# LEDs.net
KiCad netlist of a schematic drawn in Altium Designer
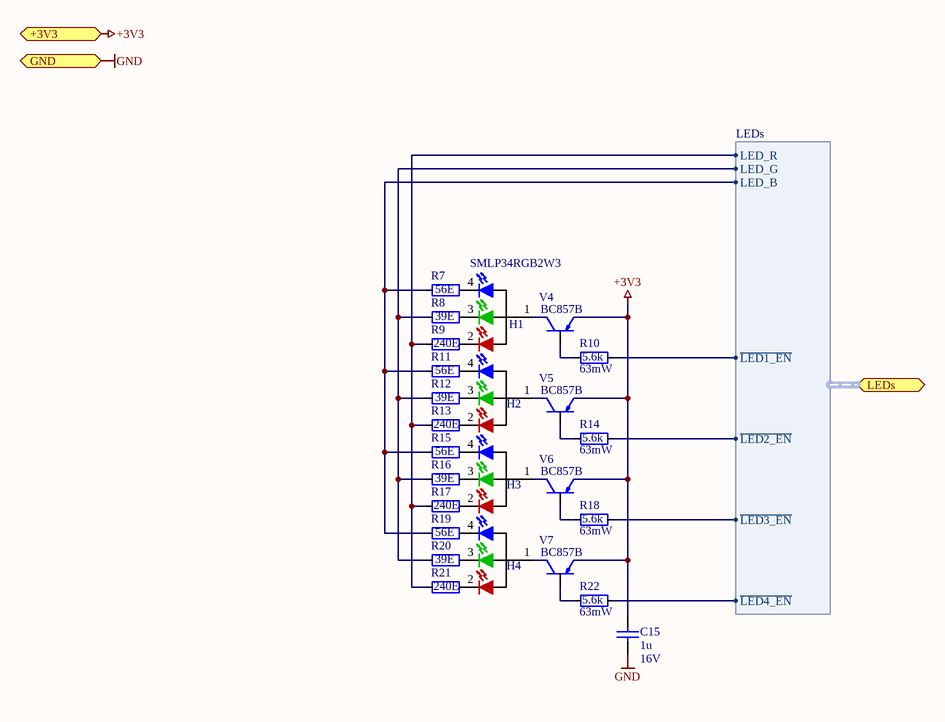
[diagram p0: LEDs.SchDoc]

(export (version "E")
  (design (tool "Eeschema 10.0.6"))
  (components
    (comp (ref "C15")
      (value "1u")
      (footprint "SMD_CAP_0603")
      (description "1µF ±10% 16V Ceramic Capacitor X7R 0603 (1608 Metric)")
      (fields (field (name "VALUE2") "16V") (field (name "Comment") "C_SMD_CER_1U_16V_10%_X7R_0603"))
      (libsource (lib "AM") (part "C_SMD_CER_1U_16V_10%_X7R_0603"))
    )
    (comp (ref "H1")
      (value "H_SMD_LED_RGB_DIFFUSED_5MA_0404")
      (footprint "SMD_LED_0404")
      (fields (field (name "TYPE") "SMLP34RGB2W3"))
      (libsource (lib "AM") (part "H_SMD_LED_RGB_DIFFUSED_5MA_0404"))
    )
    (comp (ref "H2")
      (value "H_SMD_LED_RGB_DIFFUSED_5MA_0404")
      (footprint "SMD_LED_0404")
      (libsource (lib "AM") (part "H_SMD_LED_RGB_DIFFUSED_5MA_0404"))
    )
    (comp (ref "H3")
      (value "H_SMD_LED_RGB_DIFFUSED_5MA_0404")
      (footprint "SMD_LED_0404")
      (libsource (lib "AM") (part "H_SMD_LED_RGB_DIFFUSED_5MA_0404"))
    )
    (comp (ref "H4")
      (value "H_SMD_LED_RGB_DIFFUSED_5MA_0404")
      (footprint "SMD_LED_0404")
      (libsource (lib "AM") (part "H_SMD_LED_RGB_DIFFUSED_5MA_0404"))
    )
    (comp (ref "R7")
      (value "56E")
      (footprint "SMD_RES_0402")
      (description "56 Ohms ±0.5% 0.063W, 1/16W Chip Resistor 0402 (1005 Metric) Thin Film")
      (fields (field (name "Comment") "R_SMD_THINFILM_56E_0W063_0%5_50PPM_0402"))
      (libsource (lib "AM") (part "R_SMD_THINFILM_56E_0W063_0%5_50PPM_0402"))
    )
    (comp (ref "R8")
      (value "39E")
      (footprint "SMD_RES_0402")
      (description "39 Ohms ±0.5% 0.063W, 1/16W Chip Resistor 0402 (1005 Metric) Thin Film")
      (fields (field (name "Comment") "R_SMD_THINFILM_39E_0W063_0%5_50PPM_0402"))
      (libsource (lib "AM") (part "R_SMD_THINFILM_39E_0W063_0%5_50PPM_0402"))
    )
    (comp (ref "R9")
      (value "240E")
      (footprint "SMD_RES_0402")
      (description "240 Ohms ±0.5% 0.063W, 1/16W Chip Resistor 0402 (1005 Metric) Automotive AEC-Q200 Thin Film")
      (fields (field (name "Comment") "R_SMD_THINFILM_240E_0W063_0%5_25PPM_0402"))
      (libsource (lib "AM") (part "R_SMD_THINFILM_240E_0W063_0%5_25PPM_0402"))
    )
    (comp (ref "R10")
      (value "5.6k")
      (footprint "SMD_RES_0402")
      (description "5.6 kOhms ±0.5% 0.063W, 1/16W Chip Resistor 0402 (1005 Metric) Automotive AEC-Q200 Thin Film")
      (fields
        (field (name "VALUE2") "63mW")
        (field (name "Comment") "R_SMD_THINFILM_5K6_0W063_0%5_25PPM_0402")
      )
      (libsource (lib "AM") (part "R_SMD_THINFILM_5K6_0W063_0%5_25PPM_0402"))
    )
    (comp (ref "R11")
      (value "56E")
      (footprint "SMD_RES_0402")
      (description "56 Ohms ±0.5% 0.063W, 1/16W Chip Resistor 0402 (1005 Metric) Thin Film")
      (fields (field (name "Comment") "R_SMD_THINFILM_56E_0W063_0%5_50PPM_0402"))
      (libsource (lib "AM") (part "R_SMD_THINFILM_56E_0W063_0%5_50PPM_0402"))
    )
    (comp (ref "R12")
      (value "39E")
      (footprint "SMD_RES_0402")
      (description "39 Ohms ±0.5% 0.063W, 1/16W Chip Resistor 0402 (1005 Metric) Thin Film")
      (fields (field (name "Comment") "R_SMD_THINFILM_39E_0W063_0%5_50PPM_0402"))
      (libsource (lib "AM") (part "R_SMD_THINFILM_39E_0W063_0%5_50PPM_0402"))
    )
    (comp (ref "R13")
      (value "240E")
      (footprint "SMD_RES_0402")
      (description "240 Ohms ±0.5% 0.063W, 1/16W Chip Resistor 0402 (1005 Metric) Automotive AEC-Q200 Thin Film")
      (fields (field (name "Comment") "R_SMD_THINFILM_240E_0W063_0%5_25PPM_0402"))
      (libsource (lib "AM") (part "R_SMD_THINFILM_240E_0W063_0%5_25PPM_0402"))
    )
    (comp (ref "R14")
      (value "5.6k")
      (footprint "SMD_RES_0402")
      (description "5.6 kOhms ±0.5% 0.063W, 1/16W Chip Resistor 0402 (1005 Metric) Automotive AEC-Q200 Thin Film")
      (fields
        (field (name "VALUE2") "63mW")
        (field (name "Comment") "R_SMD_THINFILM_5K6_0W063_0%5_25PPM_0402")
      )
      (libsource (lib "AM") (part "R_SMD_THINFILM_5K6_0W063_0%5_25PPM_0402"))
    )
    (comp (ref "R15")
      (value "56E")
      (footprint "SMD_RES_0402")
      (description "56 Ohms ±0.5% 0.063W, 1/16W Chip Resistor 0402 (1005 Metric) Thin Film")
      (fields (field (name "Comment") "R_SMD_THINFILM_56E_0W063_0%5_50PPM_0402"))
      (libsource (lib "AM") (part "R_SMD_THINFILM_56E_0W063_0%5_50PPM_0402"))
    )
    (comp (ref "R16")
      (value "39E")
      (footprint "SMD_RES_0402")
      (description "39 Ohms ±0.5% 0.063W, 1/16W Chip Resistor 0402 (1005 Metric) Thin Film")
      (fields (field (name "Comment") "R_SMD_THINFILM_39E_0W063_0%5_50PPM_0402"))
      (libsource (lib "AM") (part "R_SMD_THINFILM_39E_0W063_0%5_50PPM_0402"))
    )
    (comp (ref "R17")
      (value "240E")
      (footprint "SMD_RES_0402")
      (description "240 Ohms ±0.5% 0.063W, 1/16W Chip Resistor 0402 (1005 Metric) Automotive AEC-Q200 Thin Film")
      (fields (field (name "Comment") "R_SMD_THINFILM_240E_0W063_0%5_25PPM_0402"))
      (libsource (lib "AM") (part "R_SMD_THINFILM_240E_0W063_0%5_25PPM_0402"))
    )
    (comp (ref "R18")
      (value "5.6k")
      (footprint "SMD_RES_0402")
      (description "5.6 kOhms ±0.5% 0.063W, 1/16W Chip Resistor 0402 (1005 Metric) Automotive AEC-Q200 Thin Film")
      (fields
        (field (name "VALUE2") "63mW")
        (field (name "Comment") "R_SMD_THINFILM_5K6_0W063_0%5_25PPM_0402")
      )
      (libsource (lib "AM") (part "R_SMD_THINFILM_5K6_0W063_0%5_25PPM_0402"))
    )
    (comp (ref "R19")
      (value "56E")
      (footprint "SMD_RES_0402")
      (description "56 Ohms ±0.5% 0.063W, 1/16W Chip Resistor 0402 (1005 Metric) Thin Film")
      (fields (field (name "Comment") "R_SMD_THINFILM_56E_0W063_0%5_50PPM_0402"))
      (libsource (lib "AM") (part "R_SMD_THINFILM_56E_0W063_0%5_50PPM_0402"))
    )
    (comp (ref "R20")
      (value "39E")
      (footprint "SMD_RES_0402")
      (description "39 Ohms ±0.5% 0.063W, 1/16W Chip Resistor 0402 (1005 Metric) Thin Film")
      (fields (field (name "Comment") "R_SMD_THINFILM_39E_0W063_0%5_50PPM_0402"))
      (libsource (lib "AM") (part "R_SMD_THINFILM_39E_0W063_0%5_50PPM_0402"))
    )
    (comp (ref "R21")
      (value "240E")
      (footprint "SMD_RES_0402")
      (description "240 Ohms ±0.5% 0.063W, 1/16W Chip Resistor 0402 (1005 Metric) Automotive AEC-Q200 Thin Film")
      (fields (field (name "Comment") "R_SMD_THINFILM_240E_0W063_0%5_25PPM_0402"))
      (libsource (lib "AM") (part "R_SMD_THINFILM_240E_0W063_0%5_25PPM_0402"))
    )
    (comp (ref "R22")
      (value "5.6k")
      (footprint "SMD_RES_0402")
      (description "5.6 kOhms ±0.5% 0.063W, 1/16W Chip Resistor 0402 (1005 Metric) Automotive AEC-Q200 Thin Film")
      (fields
        (field (name "VALUE2") "63mW")
        (field (name "Comment") "R_SMD_THINFILM_5K6_0W063_0%5_25PPM_0402")
      )
      (libsource (lib "AM") (part "R_SMD_THINFILM_5K6_0W063_0%5_25PPM_0402"))
    )
    (comp (ref "V4")
      (value "V_SMD_TRANS_PNP_BC857B_45V_0A1_SOT-23-3")
      (footprint "SMD_SOT_23_3")
      (description "SMD PNP Transistor BC857B 100mA 45V")
      (fields (field (name "TYPE") "BC857B"))
      (libsource (lib "AM") (part "V_SMD_TRANS_PNP_BC857B_45V_0A1_SOT-23-3"))
    )
    (comp (ref "V5")
      (value "V_SMD_TRANS_PNP_BC857B_45V_0A1_SOT-23-3")
      (footprint "SMD_SOT_23_3")
      (description "SMD PNP Transistor BC857B 100mA 45V")
      (fields (field (name "TYPE") "BC857B"))
      (libsource (lib "AM") (part "V_SMD_TRANS_PNP_BC857B_45V_0A1_SOT-23-3"))
    )
    (comp (ref "V6")
      (value "V_SMD_TRANS_PNP_BC857B_45V_0A1_SOT-23-3")
      (footprint "SMD_SOT_23_3")
      (description "SMD PNP Transistor BC857B 100mA 45V")
      (fields (field (name "TYPE") "BC857B"))
      (libsource (lib "AM") (part "V_SMD_TRANS_PNP_BC857B_45V_0A1_SOT-23-3"))
    )
    (comp (ref "V7")
      (value "V_SMD_TRANS_PNP_BC857B_45V_0A1_SOT-23-3")
      (footprint "SMD_SOT_23_3")
      (description "SMD PNP Transistor BC857B 100mA 45V")
      (fields (field (name "TYPE") "BC857B"))
      (libsource (lib "AM") (part "V_SMD_TRANS_PNP_BC857B_45V_0A1_SOT-23-3"))
    )
  )
  (nets
    (net (code "2") (name "+3V3") (class "Default")
      (node (ref "C15") (pin "2") (pinfunction "2_2") (pintype "passive"))
      (node (ref "V4") (pin "2") (pinfunction "E_2") (pintype "passive"))
      (node (ref "V5") (pin "2") (pinfunction "E_2") (pintype "passive"))
      (node (ref "V6") (pin "2") (pinfunction "E_2") (pintype "passive"))
      (node (ref "V7") (pin "2") (pinfunction "E_2") (pintype "passive"))
    )
    (net (code "3") (name "/LED_B") (class "Default")
      (node (ref "R11") (pin "1") (pinfunction "1_1") (pintype "passive"))
      (node (ref "R15") (pin "1") (pinfunction "1_1") (pintype "passive"))
      (node (ref "R19") (pin "1") (pinfunction "1_1") (pintype "passive"))
      (node (ref "R7") (pin "1") (pinfunction "1_1") (pintype "passive"))
    )
    (net (code "4") (name "/LED_G") (class "Default")
      (node (ref "R12") (pin "1") (pinfunction "1_1") (pintype "passive"))
      (node (ref "R16") (pin "1") (pinfunction "1_1") (pintype "passive"))
      (node (ref "R20") (pin "1") (pinfunction "1_1") (pintype "passive"))
      (node (ref "R8") (pin "1") (pinfunction "1_1") (pintype "passive"))
    )
    (net (code "5") (name "/LED_R") (class "Default")
      (node (ref "R13") (pin "1") (pinfunction "1_1") (pintype "passive"))
      (node (ref "R17") (pin "1") (pinfunction "1_1") (pintype "passive"))
      (node (ref "R21") (pin "1") (pinfunction "1_1") (pintype "passive"))
      (node (ref "R9") (pin "1") (pinfunction "1_1") (pintype "passive"))
    )
    (net (code "7") (name "/~{LED1_EN}") (class "Default")
      (node (ref "R10") (pin "2") (pinfunction "2_2") (pintype "passive"))
    )
    (net (code "8") (name "/~{LED2_EN}") (class "Default")
      (node (ref "R14") (pin "2") (pinfunction "2_2") (pintype "passive"))
    )
    (net (code "9") (name "/~{LED3_EN}") (class "Default")
      (node (ref "R18") (pin "2") (pinfunction "2_2") (pintype "passive"))
    )
    (net (code "10") (name "/~{LED4_EN}") (class "Default")
      (node (ref "R22") (pin "2") (pinfunction "2_2") (pintype "passive"))
    )
    (net (code "11") (name "GND") (class "Default")
      (node (ref "C15") (pin "1") (pinfunction "1_1") (pintype "passive"))
    )
    (net (code "12") (name "Net-(H1-Pad2)") (class "Default")
      (node (ref "H1") (pin "2") (pinfunction "2_2") (pintype "passive"))
      (node (ref "R9") (pin "2") (pinfunction "2_2") (pintype "passive"))
    )
    (net (code "13") (name "Net-(H1-Pad3)") (class "Default")
      (node (ref "H1") (pin "3") (pinfunction "3_3") (pintype "passive"))
      (node (ref "R8") (pin "2") (pinfunction "2_2") (pintype "passive"))
    )
    (net (code "14") (name "Net-(H1-Pad4)") (class "Default")
      (node (ref "H1") (pin "4") (pinfunction "4_4") (pintype "passive"))
      (node (ref "R7") (pin "2") (pinfunction "2_2") (pintype "passive"))
    )
    (net (code "15") (name "Net-(H2-Pad2)") (class "Default")
      (node (ref "H2") (pin "2") (pinfunction "2_2") (pintype "passive"))
      (node (ref "R13") (pin "2") (pinfunction "2_2") (pintype "passive"))
    )
    (net (code "16") (name "Net-(H2-Pad3)") (class "Default")
      (node (ref "H2") (pin "3") (pinfunction "3_3") (pintype "passive"))
      (node (ref "R12") (pin "2") (pinfunction "2_2") (pintype "passive"))
    )
    (net (code "17") (name "Net-(H2-Pad4)") (class "Default")
      (node (ref "H2") (pin "4") (pinfunction "4_4") (pintype "passive"))
      (node (ref "R11") (pin "2") (pinfunction "2_2") (pintype "passive"))
    )
    (net (code "18") (name "Net-(H3-Pad2)") (class "Default")
      (node (ref "H3") (pin "2") (pinfunction "2_2") (pintype "passive"))
      (node (ref "R17") (pin "2") (pinfunction "2_2") (pintype "passive"))
    )
    (net (code "19") (name "Net-(H3-Pad3)") (class "Default")
      (node (ref "H3") (pin "3") (pinfunction "3_3") (pintype "passive"))
      (node (ref "R16") (pin "2") (pinfunction "2_2") (pintype "passive"))
    )
    (net (code "20") (name "Net-(H3-Pad4)") (class "Default")
      (node (ref "H3") (pin "4") (pinfunction "4_4") (pintype "passive"))
      (node (ref "R15") (pin "2") (pinfunction "2_2") (pintype "passive"))
    )
    (net (code "21") (name "Net-(H4-Pad2)") (class "Default")
      (node (ref "H4") (pin "2") (pinfunction "2_2") (pintype "passive"))
      (node (ref "R21") (pin "2") (pinfunction "2_2") (pintype "passive"))
    )
    (net (code "22") (name "Net-(H4-Pad3)") (class "Default")
      (node (ref "H4") (pin "3") (pinfunction "3_3") (pintype "passive"))
      (node (ref "R20") (pin "2") (pinfunction "2_2") (pintype "passive"))
    )
    (net (code "23") (name "Net-(H4-Pad4)") (class "Default")
      (node (ref "H4") (pin "4") (pinfunction "4_4") (pintype "passive"))
      (node (ref "R19") (pin "2") (pinfunction "2_2") (pintype "passive"))
    )
    (net (code "24") (name "Net-(V4-B)") (class "Default")
      (node (ref "R10") (pin "1") (pinfunction "1_1") (pintype "passive"))
      (node (ref "V4") (pin "1") (pinfunction "B_1") (pintype "passive"))
    )
    (net (code "25") (name "Net-(V4-C)") (class "Default")
      (node (ref "H1") (pin "1") (pinfunction "1_1") (pintype "passive"))
      (node (ref "V4") (pin "3") (pinfunction "C_3") (pintype "passive"))
    )
    (net (code "26") (name "Net-(V5-B)") (class "Default")
      (node (ref "R14") (pin "1") (pinfunction "1_1") (pintype "passive"))
      (node (ref "V5") (pin "1") (pinfunction "B_1") (pintype "passive"))
    )
    (net (code "27") (name "Net-(V5-C)") (class "Default")
      (node (ref "H2") (pin "1") (pinfunction "1_1") (pintype "passive"))
      (node (ref "V5") (pin "3") (pinfunction "C_3") (pintype "passive"))
    )
    (net (code "28") (name "Net-(V6-B)") (class "Default")
      (node (ref "R18") (pin "1") (pinfunction "1_1") (pintype "passive"))
      (node (ref "V6") (pin "1") (pinfunction "B_1") (pintype "passive"))
    )
    (net (code "29") (name "Net-(V6-C)") (class "Default")
      (node (ref "H3") (pin "1") (pinfunction "1_1") (pintype "passive"))
      (node (ref "V6") (pin "3") (pinfunction "C_3") (pintype "passive"))
    )
    (net (code "30") (name "Net-(V7-B)") (class "Default")
      (node (ref "R22") (pin "1") (pinfunction "1_1") (pintype "passive"))
      (node (ref "V7") (pin "1") (pinfunction "B_1") (pintype "passive"))
    )
    (net (code "31") (name "Net-(V7-C)") (class "Default")
      (node (ref "H4") (pin "1") (pinfunction "1_1") (pintype "passive"))
      (node (ref "V7") (pin "3") (pinfunction "C_3") (pintype "passive"))
    )
  )
)
